# 2018_CARTE_PUISSANCE.net
KiCad netlist of a schematic drawn in Altium Designer
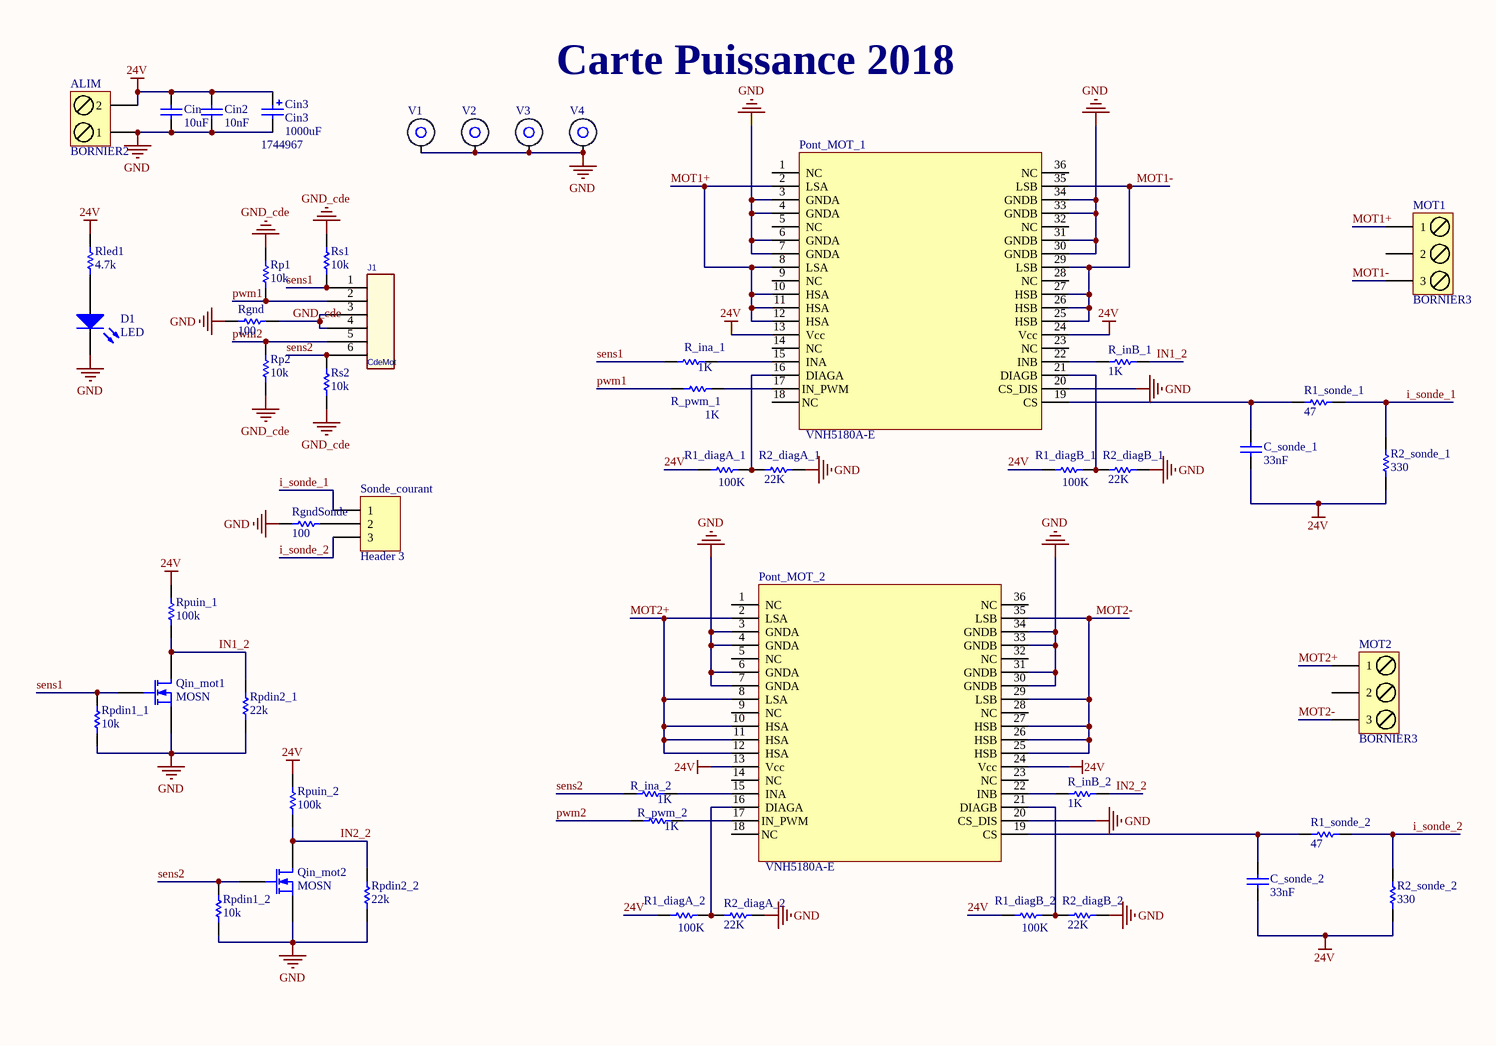
[diagram p0: 2018_CARTE_PUISSANCE.SchDoc, left]
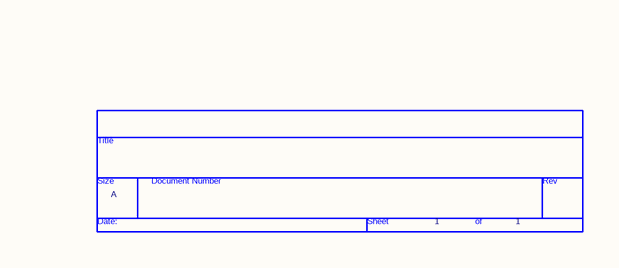
[diagram p1: 2018_CARTE_PUISSANCE.SchDoc, right]

(export (version "E")
  (design (tool "Eeschema 10.0.6"))
  (components
    (comp (ref "*")
      (value "TitleBlock0")
      (fields (field (name "PAGE COUNT") "1") (field (name "PAGE NUMBER") "1") (field (name "PAGE SIZE") "A"))
      (libsource (lib "*") (part "TitleBlock0"))
    )
    (comp (ref "ALIM")
      (value "BORNIER2")
      (footprint "BORNIER2_MALE_DROIT")
      (description "Terminal blocks, 2 pins, pitch=5mm")
      (libsource (lib "Robot2010") (part "BORNIER2"))
    )
    (comp (ref "Cin")
      (value "10uF")
      (footprint "C1206_N")
      (description "Capacitor")
      (fields (field (name "PUBLISHER") "Altium Limited"))
      (libsource (lib "DG_Condensateur") (part "Capacitor"))
    )
    (comp (ref "Cin2")
      (value "10nF")
      (footprint "C0805_N")
      (description "Capacitor")
      (fields (field (name "PUBLISHER") "Altium Limited"))
      (libsource (lib "DG_Condensateur") (part "Capacitor"))
    )
    (comp (ref "Cin3")
      (value "Cin3")
      (footprint "COND_POL_RAD_5.08B")
      (description "Polarized Capacitor")
      (fields
        (field (name "ALTIUM_VALUE") "1000uF")
        (field (name "FAR") "1744967")
        (field (name "PUBLISHER") "Altium Limited")
      )
      (libsource (lib "Robot2010") (part "CONDENSATEUR_POLARISE"))
    )
    (comp (ref "C_sonde_1")
      (value "33nF")
      (footprint "C0603_N")
      (description "Capacitor")
      (fields (field (name "PUBLISHER") "Altium Limited"))
      (libsource (lib "_ROBOT") (part "Condensateur"))
    )
    (comp (ref "C_sonde_2")
      (value "33nF")
      (footprint "C0603_N")
      (description "Capacitor")
      (fields (field (name "PUBLISHER") "Altium Limited"))
      (libsource (lib "_ROBOT") (part "Condensateur"))
    )
    (comp (ref "D1")
      (value "LED")
      (footprint "LED_0805")
      (description "Typical LED")
      (fields (field (name "PUBLISHER") "Altium Limited"))
      (libsource (lib "DG_LED") (part "LED"))
    )
    (comp (ref "J1") (value "CdeMot") (footprint "RJ11_6/6") (libsource (lib "*") (part "CONNECTEUR_RJ12")))
    (comp (ref "MOT1")
      (value "BORNIER3")
      (footprint "BORNIER3")
      (description "Terminal blocks, 2 pins, pitch=5mm")
      (libsource (lib "Connecteur") (part "BORNIER3"))
    )
    (comp (ref "MOT2")
      (value "BORNIER3")
      (footprint "BORNIER3")
      (description "Terminal blocks, 2 pins, pitch=5mm")
      (libsource (lib "Connecteur") (part "BORNIER3"))
    )
    (comp (ref "Pont_MOT_1")
      (value "VNH5180A-E")
      (footprint "PowerSSO-36 TP")
      (fields (field (name "TYPE") "VNH5180A-E"))
      (libsource (lib "Circuit intégré") (part "VNH5180A-E"))
    )
    (comp (ref "Pont_MOT_2")
      (value "VNH5180A-E")
      (footprint "PowerSSO-36 TP")
      (fields (field (name "TYPE") "VNH5180A-E"))
      (libsource (lib "Circuit intégré") (part "VNH5180A-E"))
    )
    (comp (ref "Qin_mot1")
      (value "MOSN")
      (footprint "SOT23-3N")
      (description "N-Channel MOSFET")
      (fields (field (name "PUBLISHER") "Altium Limited"))
      (libsource (lib "_ROBOT") (part "Transistor MOSFET-N"))
    )
    (comp (ref "Qin_mot2")
      (value "MOSN")
      (footprint "SOT23-3N")
      (description "N-Channel MOSFET")
      (fields (field (name "PUBLISHER") "Altium Limited"))
      (libsource (lib "_ROBOT") (part "Transistor MOSFET-N"))
    )
    (comp (ref "R1_diagA_1")
      (value "100K")
      (footprint "R1206_N")
      (description "Resistor")
      (fields (field (name "PUBLISHER") "Altium Limited"))
      (libsource (lib "_ROBOT") (part "Resistor"))
    )
    (comp (ref "R1_diagA_2")
      (value "100K")
      (footprint "R1206_N")
      (description "Resistor")
      (fields (field (name "PUBLISHER") "Altium Limited"))
      (libsource (lib "_ROBOT") (part "Resistor"))
    )
    (comp (ref "R1_diagB_1")
      (value "100K")
      (footprint "R1206_N")
      (description "Resistor")
      (fields (field (name "PUBLISHER") "Altium Limited"))
      (libsource (lib "_ROBOT") (part "Resistor"))
    )
    (comp (ref "R1_diagB_2")
      (value "100K")
      (footprint "R1206_N")
      (description "Resistor")
      (fields (field (name "PUBLISHER") "Altium Limited"))
      (libsource (lib "_ROBOT") (part "Resistor"))
    )
    (comp (ref "R1_sonde_1")
      (value "47")
      (footprint "R1206_N")
      (description "Resistor")
      (fields (field (name "PUBLISHER") "Altium Limited"))
      (libsource (lib "_ROBOT") (part "Resistor"))
    )
    (comp (ref "R1_sonde_2")
      (value "47")
      (footprint "R1206_N")
      (description "Resistor")
      (fields (field (name "PUBLISHER") "Altium Limited"))
      (libsource (lib "_ROBOT") (part "Resistor"))
    )
    (comp (ref "R2_diagA_1")
      (value "22K")
      (footprint "R1206_N")
      (description "Resistor")
      (fields (field (name "PUBLISHER") "Altium Limited"))
      (libsource (lib "_ROBOT") (part "Resistor"))
    )
    (comp (ref "R2_diagA_2")
      (value "22K")
      (footprint "R1206_N")
      (description "Resistor")
      (fields (field (name "PUBLISHER") "Altium Limited"))
      (libsource (lib "_ROBOT") (part "Resistor"))
    )
    (comp (ref "R2_diagB_1")
      (value "22K")
      (footprint "R1206_N")
      (description "Resistor")
      (fields (field (name "PUBLISHER") "Altium Limited"))
      (libsource (lib "_ROBOT") (part "Resistor"))
    )
    (comp (ref "R2_diagB_2")
      (value "22K")
      (footprint "R1206_N")
      (description "Resistor")
      (fields (field (name "PUBLISHER") "Altium Limited"))
      (libsource (lib "_ROBOT") (part "Resistor"))
    )
    (comp (ref "R2_sonde_1")
      (value "330")
      (footprint "R1206_N")
      (description "Resistor")
      (fields (field (name "PUBLISHER") "Altium Limited"))
      (libsource (lib "_ROBOT") (part "Resistor"))
    )
    (comp (ref "R2_sonde_2")
      (value "330")
      (footprint "R1206_N")
      (description "Resistor")
      (fields (field (name "PUBLISHER") "Altium Limited"))
      (libsource (lib "_ROBOT") (part "Resistor"))
    )
    (comp (ref "Rgnd")
      (value "100")
      (footprint "R1206_N")
      (description "Resistor")
      (fields (field (name "PUBLISHER") "Altium Limited"))
      (libsource (lib "DG_Resistance") (part "Resistor"))
    )
    (comp (ref "RgndSonde")
      (value "100")
      (footprint "R1206_N")
      (description "Resistor")
      (fields (field (name "PUBLISHER") "Altium Limited"))
      (libsource (lib "DG_Resistance") (part "Resistor"))
    )
    (comp (ref "Rled1")
      (value "4.7k")
      (footprint "R1206_N")
      (description "Resistor")
      (fields (field (name "PUBLISHER") "Altium Limited"))
      (libsource (lib "DG_Resistance") (part "Resistor"))
    )
    (comp (ref "Rp1")
      (value "10k")
      (footprint "R1206_N")
      (description "Resistor")
      (fields (field (name "PUBLISHER") "Altium Limited"))
      (libsource (lib "DG_Resistance") (part "Resistor"))
    )
    (comp (ref "Rp2")
      (value "10k")
      (footprint "R1206_N")
      (description "Resistor")
      (fields (field (name "PUBLISHER") "Altium Limited"))
      (libsource (lib "DG_Resistance") (part "Resistor"))
    )
    (comp (ref "Rpdin1_1")
      (value "10k")
      (footprint "R1206_N")
      (description "Resistor")
      (fields (field (name "PUBLISHER") "Altium Limited"))
      (libsource (lib "DG_Resistance") (part "Resistor"))
    )
    (comp (ref "Rpdin1_2")
      (value "10k")
      (footprint "R1206_N")
      (description "Resistor")
      (fields (field (name "PUBLISHER") "Altium Limited"))
      (libsource (lib "DG_Resistance") (part "Resistor"))
    )
    (comp (ref "Rpdin2_1")
      (value "22k")
      (footprint "R1206_N")
      (description "Resistor")
      (fields (field (name "PUBLISHER") "Altium Limited"))
      (libsource (lib "DG_Resistance") (part "Resistor"))
    )
    (comp (ref "Rpdin2_2")
      (value "22k")
      (footprint "R1206_N")
      (description "Resistor")
      (fields (field (name "PUBLISHER") "Altium Limited"))
      (libsource (lib "DG_Resistance") (part "Resistor"))
    )
    (comp (ref "Rpuin_1")
      (value "100k")
      (footprint "R1206_N")
      (description "Resistor")
      (fields (field (name "PUBLISHER") "Altium Limited"))
      (libsource (lib "DG_Resistance") (part "Resistor"))
    )
    (comp (ref "Rpuin_2")
      (value "100k")
      (footprint "R1206_N")
      (description "Resistor")
      (fields (field (name "PUBLISHER") "Altium Limited"))
      (libsource (lib "DG_Resistance") (part "Resistor"))
    )
    (comp (ref "Rs1")
      (value "10k")
      (footprint "R1206_N")
      (description "Resistor")
      (fields (field (name "PUBLISHER") "Altium Limited"))
      (libsource (lib "DG_Resistance") (part "Resistor"))
    )
    (comp (ref "Rs2")
      (value "10k")
      (footprint "R1206_N")
      (description "Resistor")
      (fields (field (name "PUBLISHER") "Altium Limited"))
      (libsource (lib "DG_Resistance") (part "Resistor"))
    )
    (comp (ref "R_ina_1")
      (value "1K")
      (footprint "R1206_N")
      (description "Resistor")
      (fields (field (name "PUBLISHER") "Altium Limited"))
      (libsource (lib "_ROBOT") (part "Resistor"))
    )
    (comp (ref "R_ina_2")
      (value "1K")
      (footprint "R1206_N")
      (description "Resistor")
      (fields (field (name "PUBLISHER") "Altium Limited"))
      (libsource (lib "_ROBOT") (part "Resistor"))
    )
    (comp (ref "R_inB_1")
      (value "1K")
      (footprint "R1206_N")
      (description "Resistor")
      (fields (field (name "PUBLISHER") "Altium Limited"))
      (libsource (lib "_ROBOT") (part "Resistor"))
    )
    (comp (ref "R_inB_2")
      (value "1K")
      (footprint "R1206_N")
      (description "Resistor")
      (fields (field (name "PUBLISHER") "Altium Limited"))
      (libsource (lib "_ROBOT") (part "Resistor"))
    )
    (comp (ref "R_pwm_1")
      (value "1K")
      (footprint "R1206_N")
      (description "Resistor")
      (fields (field (name "PUBLISHER") "Altium Limited"))
      (libsource (lib "_ROBOT") (part "Resistor"))
    )
    (comp (ref "R_pwm_2")
      (value "1K")
      (footprint "R1206_N")
      (description "Resistor")
      (fields (field (name "PUBLISHER") "Altium Limited"))
      (libsource (lib "_ROBOT") (part "Resistor"))
    )
    (comp (ref "Sonde_courant")
      (value "Header 3")
      (footprint "HDR1X3")
      (description "Header, 3-Pin")
      (fields (field (name "PUBLISHER") "Altium Limited"))
      (libsource (lib "DG_Connecteur") (part "Header 3"))
    )
    (comp (ref "V1")
      (value "Entretoise WURTH CMS")
      (footprint "ENTRETOISE_CMS")
      (description "Entretoise Wurth")
      (fields (field (name "PUBLISHER") "Damien Guitton"))
      (libsource (lib "_ROBOT") (part "Entretoise WURTH CMS"))
    )
    (comp (ref "V2")
      (value "Entretoise WURTH CMS")
      (footprint "ENTRETOISE_CMS")
      (description "Entretoise Wurth")
      (fields (field (name "PUBLISHER") "Damien Guitton"))
      (libsource (lib "_ROBOT") (part "Entretoise WURTH CMS"))
    )
    (comp (ref "V3")
      (value "Entretoise WURTH CMS")
      (footprint "ENTRETOISE_CMS")
      (description "Entretoise Wurth")
      (fields (field (name "PUBLISHER") "Damien Guitton"))
      (libsource (lib "_ROBOT") (part "Entretoise WURTH CMS"))
    )
    (comp (ref "V4")
      (value "Entretoise WURTH CMS")
      (footprint "ENTRETOISE_CMS")
      (description "Entretoise Wurth")
      (fields (field (name "PUBLISHER") "Damien Guitton"))
      (libsource (lib "_ROBOT") (part "Entretoise WURTH CMS"))
    )
  )
  (nets
    (net (code "1") (name "/IN1_2") (class "Default")
      (node (ref "Qin_mot1") (pin "3") (pinfunction "D_3") (pintype "passive"))
      (node (ref "R_inB_1") (pin "2") (pinfunction "2_2") (pintype "passive"))
      (node (ref "Rpdin2_1") (pin "2") (pinfunction "2_2") (pintype "passive"))
      (node (ref "Rpuin_1") (pin "1") (pinfunction "1_1") (pintype "passive"))
    )
    (net (code "2") (name "/IN2_2") (class "Default")
      (node (ref "Qin_mot2") (pin "3") (pinfunction "D_3") (pintype "passive"))
      (node (ref "R_inB_2") (pin "2") (pinfunction "2_2") (pintype "passive"))
      (node (ref "Rpdin2_2") (pin "2") (pinfunction "2_2") (pintype "passive"))
      (node (ref "Rpuin_2") (pin "1") (pinfunction "1_1") (pintype "passive"))
    )
    (net (code "3") (name "/MOT1+") (class "Default")
      (node (ref "MOT1") (pin "1") (pinfunction "1_1") (pintype "passive"))
      (node (ref "Pont_MOT_1") (pin "10") (pinfunction "HSA_10") (pintype "passive"))
      (node (ref "Pont_MOT_1") (pin "11") (pinfunction "HSA_11") (pintype "passive"))
      (node (ref "Pont_MOT_1") (pin "12") (pinfunction "HSA_12") (pintype "passive"))
      (node (ref "Pont_MOT_1") (pin "2") (pinfunction "LSA_2") (pintype "passive"))
      (node (ref "Pont_MOT_1") (pin "8") (pinfunction "LSA_8") (pintype "passive"))
    )
    (net (code "4") (name "/MOT1-") (class "Default")
      (node (ref "MOT1") (pin "3") (pinfunction "3_3") (pintype "passive"))
      (node (ref "Pont_MOT_1") (pin "25") (pinfunction "HSB_25") (pintype "passive"))
      (node (ref "Pont_MOT_1") (pin "26") (pinfunction "HSB_26") (pintype "passive"))
      (node (ref "Pont_MOT_1") (pin "27") (pinfunction "HSB_27") (pintype "passive"))
      (node (ref "Pont_MOT_1") (pin "29") (pinfunction "LSB_29") (pintype "passive"))
      (node (ref "Pont_MOT_1") (pin "35") (pinfunction "LSB_35") (pintype "passive"))
    )
    (net (code "5") (name "/MOT2+") (class "Default")
      (node (ref "MOT2") (pin "1") (pinfunction "1_1") (pintype "passive"))
      (node (ref "Pont_MOT_2") (pin "10") (pinfunction "HSA_10") (pintype "passive"))
      (node (ref "Pont_MOT_2") (pin "11") (pinfunction "HSA_11") (pintype "passive"))
      (node (ref "Pont_MOT_2") (pin "12") (pinfunction "HSA_12") (pintype "passive"))
      (node (ref "Pont_MOT_2") (pin "2") (pinfunction "LSA_2") (pintype "passive"))
      (node (ref "Pont_MOT_2") (pin "8") (pinfunction "LSA_8") (pintype "passive"))
    )
    (net (code "6") (name "/MOT2-") (class "Default")
      (node (ref "MOT2") (pin "3") (pinfunction "3_3") (pintype "passive"))
      (node (ref "Pont_MOT_2") (pin "25") (pinfunction "HSB_25") (pintype "passive"))
      (node (ref "Pont_MOT_2") (pin "26") (pinfunction "HSB_26") (pintype "passive"))
      (node (ref "Pont_MOT_2") (pin "27") (pinfunction "HSB_27") (pintype "passive"))
      (node (ref "Pont_MOT_2") (pin "29") (pinfunction "LSB_29") (pintype "passive"))
      (node (ref "Pont_MOT_2") (pin "35") (pinfunction "LSB_35") (pintype "passive"))
    )
    (net (code "7") (name "/i_sonde_1") (class "Default")
      (node (ref "R1_sonde_1") (pin "2") (pinfunction "2_2") (pintype "passive"))
      (node (ref "R2_sonde_1") (pin "2") (pinfunction "2_2") (pintype "passive"))
      (node (ref "Sonde_courant") (pin "1") (pinfunction "1_1") (pintype "passive"))
    )
    (net (code "8") (name "/i_sonde_2") (class "Default")
      (node (ref "R1_sonde_2") (pin "2") (pinfunction "2_2") (pintype "passive"))
      (node (ref "R2_sonde_2") (pin "2") (pinfunction "2_2") (pintype "passive"))
      (node (ref "Sonde_courant") (pin "3") (pinfunction "3_3") (pintype "passive"))
    )
    (net (code "9") (name "/pwm1") (class "Default")
      (node (ref "J1") (pin "2") (pinfunction "2_2") (pintype "passive"))
      (node (ref "R_pwm_1") (pin "1") (pinfunction "1_1") (pintype "passive"))
      (node (ref "Rp1") (pin "1") (pinfunction "1_1") (pintype "passive"))
    )
    (net (code "10") (name "/pwm2") (class "Default")
      (node (ref "J1") (pin "5") (pinfunction "5_5") (pintype "passive"))
      (node (ref "R_pwm_2") (pin "1") (pinfunction "1_1") (pintype "passive"))
      (node (ref "Rp2") (pin "2") (pinfunction "2_2") (pintype "passive"))
    )
    (net (code "11") (name "/sens1") (class "Default")
      (node (ref "J1") (pin "1") (pinfunction "1_1") (pintype "passive"))
      (node (ref "Qin_mot1") (pin "1") (pinfunction "G_1") (pintype "passive"))
      (node (ref "R_ina_1") (pin "1") (pinfunction "1_1") (pintype "passive"))
      (node (ref "Rpdin1_1") (pin "1") (pinfunction "1_1") (pintype "passive"))
      (node (ref "Rs1") (pin "1") (pinfunction "1_1") (pintype "passive"))
    )
    (net (code "12") (name "/sens2") (class "Default")
      (node (ref "J1") (pin "6") (pinfunction "6_6") (pintype "passive"))
      (node (ref "Qin_mot2") (pin "1") (pinfunction "G_1") (pintype "passive"))
      (node (ref "R_ina_2") (pin "1") (pinfunction "1_1") (pintype "passive"))
      (node (ref "Rpdin1_2") (pin "1") (pinfunction "1_1") (pintype "passive"))
      (node (ref "Rs2") (pin "2") (pinfunction "2_2") (pintype "passive"))
    )
    (net (code "13") (name "24V") (class "Default")
      (node (ref "ALIM") (pin "2") (pinfunction "2_2") (pintype "passive"))
      (node (ref "C_sonde_1") (pin "1") (pinfunction "1_1") (pintype "passive"))
      (node (ref "C_sonde_2") (pin "1") (pinfunction "1_1") (pintype "passive"))
      (node (ref "Cin") (pin "2") (pinfunction "2_2") (pintype "passive"))
      (node (ref "Cin2") (pin "2") (pinfunction "2_2") (pintype "passive"))
      (node (ref "Cin3") (pin "1") (pinfunction "1_1") (pintype "passive"))
      (node (ref "Pont_MOT_1") (pin "13") (pinfunction "Vcc_13") (pintype "passive"))
      (node (ref "Pont_MOT_1") (pin "24") (pinfunction "Vcc_24") (pintype "passive"))
      (node (ref "Pont_MOT_2") (pin "13") (pinfunction "Vcc_13") (pintype "passive"))
      (node (ref "Pont_MOT_2") (pin "24") (pinfunction "Vcc_24") (pintype "passive"))
      (node (ref "R1_diagA_1") (pin "1") (pinfunction "1_1") (pintype "passive"))
      (node (ref "R1_diagA_2") (pin "1") (pinfunction "1_1") (pintype "passive"))
      (node (ref "R1_diagB_1") (pin "1") (pinfunction "1_1") (pintype "passive"))
      (node (ref "R1_diagB_2") (pin "1") (pinfunction "1_1") (pintype "passive"))
      (node (ref "R2_sonde_1") (pin "1") (pinfunction "1_1") (pintype "passive"))
      (node (ref "R2_sonde_2") (pin "1") (pinfunction "1_1") (pintype "passive"))
      (node (ref "Rled1") (pin "2") (pinfunction "2_2") (pintype "passive"))
      (node (ref "Rpuin_1") (pin "2") (pinfunction "2_2") (pintype "passive"))
      (node (ref "Rpuin_2") (pin "2") (pinfunction "2_2") (pintype "passive"))
    )
    (net (code "14") (name "GND") (class "Default")
      (node (ref "ALIM") (pin "1") (pinfunction "1_1") (pintype "passive"))
      (node (ref "Cin") (pin "1") (pinfunction "1_1") (pintype "passive"))
      (node (ref "Cin2") (pin "1") (pinfunction "1_1") (pintype "passive"))
      (node (ref "Cin3") (pin "2") (pinfunction "2_2") (pintype "passive"))
      (node (ref "D1") (pin "2") (pinfunction "2_2") (pintype "passive"))
      (node (ref "Pont_MOT_1") (pin "20") (pinfunction "CS_DIS_20") (pintype "passive"))
      (node (ref "Pont_MOT_1") (pin "3") (pinfunction "GNDA_3") (pintype "passive"))
      (node (ref "Pont_MOT_1") (pin "30") (pinfunction "GNDB_30") (pintype "passive"))
      (node (ref "Pont_MOT_1") (pin "31") (pinfunction "GNDB_31") (pintype "passive"))
      (node (ref "Pont_MOT_1") (pin "33") (pinfunction "GNDB_33") (pintype "passive"))
      (node (ref "Pont_MOT_1") (pin "34") (pinfunction "GNDB_34") (pintype "passive"))
      (node (ref "Pont_MOT_1") (pin "4") (pinfunction "GNDA_4") (pintype "passive"))
      (node (ref "Pont_MOT_1") (pin "6") (pinfunction "GNDA_6") (pintype "passive"))
      (node (ref "Pont_MOT_1") (pin "7") (pinfunction "GNDA_7") (pintype "passive"))
      (node (ref "Pont_MOT_2") (pin "20") (pinfunction "CS_DIS_20") (pintype "passive"))
      (node (ref "Pont_MOT_2") (pin "3") (pinfunction "GNDA_3") (pintype "passive"))
      (node (ref "Pont_MOT_2") (pin "30") (pinfunction "GNDB_30") (pintype "passive"))
      (node (ref "Pont_MOT_2") (pin "31") (pinfunction "GNDB_31") (pintype "passive"))
      (node (ref "Pont_MOT_2") (pin "33") (pinfunction "GNDB_33") (pintype "passive"))
      (node (ref "Pont_MOT_2") (pin "34") (pinfunction "GNDB_34") (pintype "passive"))
      (node (ref "Pont_MOT_2") (pin "4") (pinfunction "GNDA_4") (pintype "passive"))
      (node (ref "Pont_MOT_2") (pin "6") (pinfunction "GNDA_6") (pintype "passive"))
      (node (ref "Pont_MOT_2") (pin "7") (pinfunction "GNDA_7") (pintype "passive"))
      (node (ref "Qin_mot1") (pin "2") (pinfunction "S_2") (pintype "passive"))
      (node (ref "Qin_mot2") (pin "2") (pinfunction "S_2") (pintype "passive"))
      (node (ref "R2_diagA_1") (pin "2") (pinfunction "2_2") (pintype "passive"))
      (node (ref "R2_diagA_2") (pin "2") (pinfunction "2_2") (pintype "passive"))
      (node (ref "R2_diagB_1") (pin "2") (pinfunction "2_2") (pintype "passive"))
      (node (ref "R2_diagB_2") (pin "2") (pinfunction "2_2") (pintype "passive"))
      (node (ref "Rgnd") (pin "2") (pinfunction "2_2") (pintype "passive"))
      (node (ref "RgndSonde") (pin "2") (pinfunction "2_2") (pintype "passive"))
      (node (ref "Rpdin1_1") (pin "2") (pinfunction "2_2") (pintype "passive"))
      (node (ref "Rpdin1_2") (pin "2") (pinfunction "2_2") (pintype "passive"))
      (node (ref "Rpdin2_1") (pin "1") (pinfunction "1_1") (pintype "passive"))
      (node (ref "Rpdin2_2") (pin "1") (pinfunction "1_1") (pintype "passive"))
      (node (ref "V1") (pin "1") (pinfunction "1_1") (pintype "passive"))
      (node (ref "V2") (pin "1") (pinfunction "1_1") (pintype "passive"))
      (node (ref "V3") (pin "1") (pinfunction "1_1") (pintype "passive"))
      (node (ref "V4") (pin "1") (pinfunction "1_1") (pintype "passive"))
    )
    (net (code "15") (name "GND_cde") (class "Default")
      (node (ref "J1") (pin "3") (pinfunction "3_3") (pintype "passive"))
      (node (ref "J1") (pin "4") (pinfunction "4_4") (pintype "passive"))
      (node (ref "Rgnd") (pin "1") (pinfunction "1_1") (pintype "passive"))
      (node (ref "Rp1") (pin "2") (pinfunction "2_2") (pintype "passive"))
      (node (ref "Rp2") (pin "1") (pinfunction "1_1") (pintype "passive"))
      (node (ref "Rs1") (pin "2") (pinfunction "2_2") (pintype "passive"))
      (node (ref "Rs2") (pin "1") (pinfunction "1_1") (pintype "passive"))
    )
    (net (code "16") (name "Net-(D1-Pad1)") (class "Default")
      (node (ref "D1") (pin "1") (pinfunction "1_1") (pintype "passive"))
      (node (ref "Rled1") (pin "1") (pinfunction "1_1") (pintype "passive"))
    )
    (net (code "17") (name "Net-(Pont_MOT_1-CS)") (class "Default")
      (node (ref "C_sonde_1") (pin "2") (pinfunction "2_2") (pintype "passive"))
      (node (ref "Pont_MOT_1") (pin "19") (pinfunction "CS_19") (pintype "passive"))
      (node (ref "R1_sonde_1") (pin "1") (pinfunction "1_1") (pintype "passive"))
    )
    (net (code "18") (name "Net-(Pont_MOT_1-DIAGA)") (class "Default")
      (node (ref "Pont_MOT_1") (pin "16") (pinfunction "DIAGA_16") (pintype "passive"))
      (node (ref "R1_diagA_1") (pin "2") (pinfunction "2_2") (pintype "passive"))
      (node (ref "R2_diagA_1") (pin "1") (pinfunction "1_1") (pintype "passive"))
    )
    (net (code "19") (name "Net-(Pont_MOT_1-DIAGB)") (class "Default")
      (node (ref "Pont_MOT_1") (pin "21") (pinfunction "DIAGB_21") (pintype "passive"))
      (node (ref "R1_diagB_1") (pin "2") (pinfunction "2_2") (pintype "passive"))
      (node (ref "R2_diagB_1") (pin "1") (pinfunction "1_1") (pintype "passive"))
    )
    (net (code "20") (name "Net-(Pont_MOT_1-INA)") (class "Default")
      (node (ref "Pont_MOT_1") (pin "15") (pinfunction "INA_15") (pintype "passive"))
      (node (ref "R_ina_1") (pin "2") (pinfunction "2_2") (pintype "passive"))
    )
    (net (code "21") (name "Net-(Pont_MOT_1-INB)") (class "Default")
      (node (ref "Pont_MOT_1") (pin "22") (pinfunction "INB_22") (pintype "passive"))
      (node (ref "R_inB_1") (pin "1") (pinfunction "1_1") (pintype "passive"))
    )
    (net (code "22") (name "Net-(Pont_MOT_1-IN_PWM)") (class "Default")
      (node (ref "Pont_MOT_1") (pin "17") (pinfunction "IN_PWM_17") (pintype "passive"))
      (node (ref "R_pwm_1") (pin "2") (pinfunction "2_2") (pintype "passive"))
    )
    (net (code "23") (name "Net-(Pont_MOT_2-CS)") (class "Default")
      (node (ref "C_sonde_2") (pin "2") (pinfunction "2_2") (pintype "passive"))
      (node (ref "Pont_MOT_2") (pin "19") (pinfunction "CS_19") (pintype "passive"))
      (node (ref "R1_sonde_2") (pin "1") (pinfunction "1_1") (pintype "passive"))
    )
    (net (code "24") (name "Net-(Pont_MOT_2-DIAGA)") (class "Default")
      (node (ref "Pont_MOT_2") (pin "16") (pinfunction "DIAGA_16") (pintype "passive"))
      (node (ref "R1_diagA_2") (pin "2") (pinfunction "2_2") (pintype "passive"))
      (node (ref "R2_diagA_2") (pin "1") (pinfunction "1_1") (pintype "passive"))
    )
    (net (code "25") (name "Net-(Pont_MOT_2-DIAGB)") (class "Default")
      (node (ref "Pont_MOT_2") (pin "21") (pinfunction "DIAGB_21") (pintype "passive"))
      (node (ref "R1_diagB_2") (pin "2") (pinfunction "2_2") (pintype "passive"))
      (node (ref "R2_diagB_2") (pin "1") (pinfunction "1_1") (pintype "passive"))
    )
    (net (code "26") (name "Net-(Pont_MOT_2-INA)") (class "Default")
      (node (ref "Pont_MOT_2") (pin "15") (pinfunction "INA_15") (pintype "passive"))
      (node (ref "R_ina_2") (pin "2") (pinfunction "2_2") (pintype "passive"))
    )
    (net (code "27") (name "Net-(Pont_MOT_2-INB)") (class "Default")
      (node (ref "Pont_MOT_2") (pin "22") (pinfunction "INB_22") (pintype "passive"))
      (node (ref "R_inB_2") (pin "1") (pinfunction "1_1") (pintype "passive"))
    )
    (net (code "28") (name "Net-(Pont_MOT_2-IN_PWM)") (class "Default")
      (node (ref "Pont_MOT_2") (pin "17") (pinfunction "IN_PWM_17") (pintype "passive"))
      (node (ref "R_pwm_2") (pin "2") (pinfunction "2_2") (pintype "passive"))
    )
    (net (code "29") (name "Net-(RgndSonde-Pad1)") (class "Default")
      (node (ref "RgndSonde") (pin "1") (pinfunction "1_1") (pintype "passive"))
      (node (ref "Sonde_courant") (pin "2") (pinfunction "2_2") (pintype "passive"))
    )
    (net (code "30") (name "unconnected-(MOT1-Pad2)") (class "Default")
      (node (ref "MOT1") (pin "2") (pinfunction "2_2") (pintype "passive"))
    )
    (net (code "31") (name "unconnected-(MOT2-Pad2)") (class "Default")
      (node (ref "MOT2") (pin "2") (pinfunction "2_2") (pintype "passive"))
    )
    (net (code "32") (name "unconnected-(Pont_MOT_1-NC-Pad1)") (class "Default")
      (node (ref "Pont_MOT_1") (pin "1") (pinfunction "NC_1") (pintype "passive"))
    )
    (net (code "33") (name "unconnected-(Pont_MOT_1-NC-Pad5)") (class "Default")
      (node (ref "Pont_MOT_1") (pin "5") (pinfunction "NC_5") (pintype "passive"))
    )
    (net (code "34") (name "unconnected-(Pont_MOT_1-NC-Pad9)") (class "Default")
      (node (ref "Pont_MOT_1") (pin "9") (pinfunction "NC_9") (pintype "passive"))
    )
    (net (code "35") (name "unconnected-(Pont_MOT_1-NC-Pad14)") (class "Default")
      (node (ref "Pont_MOT_1") (pin "14") (pinfunction "NC_14") (pintype "passive"))
    )
    (net (code "36") (name "unconnected-(Pont_MOT_1-NC-Pad18)") (class "Default")
      (node (ref "Pont_MOT_1") (pin "18") (pinfunction "NC_18") (pintype "passive"))
    )
    (net (code "37") (name "unconnected-(Pont_MOT_1-NC-Pad23)") (class "Default")
      (node (ref "Pont_MOT_1") (pin "23") (pinfunction "NC_23") (pintype "passive"))
    )
    (net (code "38") (name "unconnected-(Pont_MOT_1-NC-Pad28)") (class "Default")
      (node (ref "Pont_MOT_1") (pin "28") (pinfunction "NC_28") (pintype "passive"))
    )
    (net (code "39") (name "unconnected-(Pont_MOT_1-NC-Pad32)") (class "Default")
      (node (ref "Pont_MOT_1") (pin "32") (pinfunction "NC_32") (pintype "passive"))
    )
    (net (code "40") (name "unconnected-(Pont_MOT_1-NC-Pad36)") (class "Default")
      (node (ref "Pont_MOT_1") (pin "36") (pinfunction "NC_36") (pintype "passive"))
    )
    (net (code "41") (name "unconnected-(Pont_MOT_2-NC-Pad1)") (class "Default")
      (node (ref "Pont_MOT_2") (pin "1") (pinfunction "NC_1") (pintype "passive"))
    )
    (net (code "42") (name "unconnected-(Pont_MOT_2-NC-Pad5)") (class "Default")
      (node (ref "Pont_MOT_2") (pin "5") (pinfunction "NC_5") (pintype "passive"))
    )
    (net (code "43") (name "unconnected-(Pont_MOT_2-NC-Pad9)") (class "Default")
      (node (ref "Pont_MOT_2") (pin "9") (pinfunction "NC_9") (pintype "passive"))
    )
    (net (code "44") (name "unconnected-(Pont_MOT_2-NC-Pad14)") (class "Default")
      (node (ref "Pont_MOT_2") (pin "14") (pinfunction "NC_14") (pintype "passive"))
    )
    (net (code "45") (name "unconnected-(Pont_MOT_2-NC-Pad18)") (class "Default")
      (node (ref "Pont_MOT_2") (pin "18") (pinfunction "NC_18") (pintype "passive"))
    )
    (net (code "46") (name "unconnected-(Pont_MOT_2-NC-Pad23)") (class "Default")
      (node (ref "Pont_MOT_2") (pin "23") (pinfunction "NC_23") (pintype "passive"))
    )
    (net (code "47") (name "unconnected-(Pont_MOT_2-NC-Pad28)") (class "Default")
      (node (ref "Pont_MOT_2") (pin "28") (pinfunction "NC_28") (pintype "passive"))
    )
    (net (code "48") (name "unconnected-(Pont_MOT_2-NC-Pad32)") (class "Default")
      (node (ref "Pont_MOT_2") (pin "32") (pinfunction "NC_32") (pintype "passive"))
    )
    (net (code "49") (name "unconnected-(Pont_MOT_2-NC-Pad36)") (class "Default")
      (node (ref "Pont_MOT_2") (pin "36") (pinfunction "NC_36") (pintype "passive"))
    )
  )
)
